# PR9025.net
KiCad netlist of a schematic drawn in EAGLE
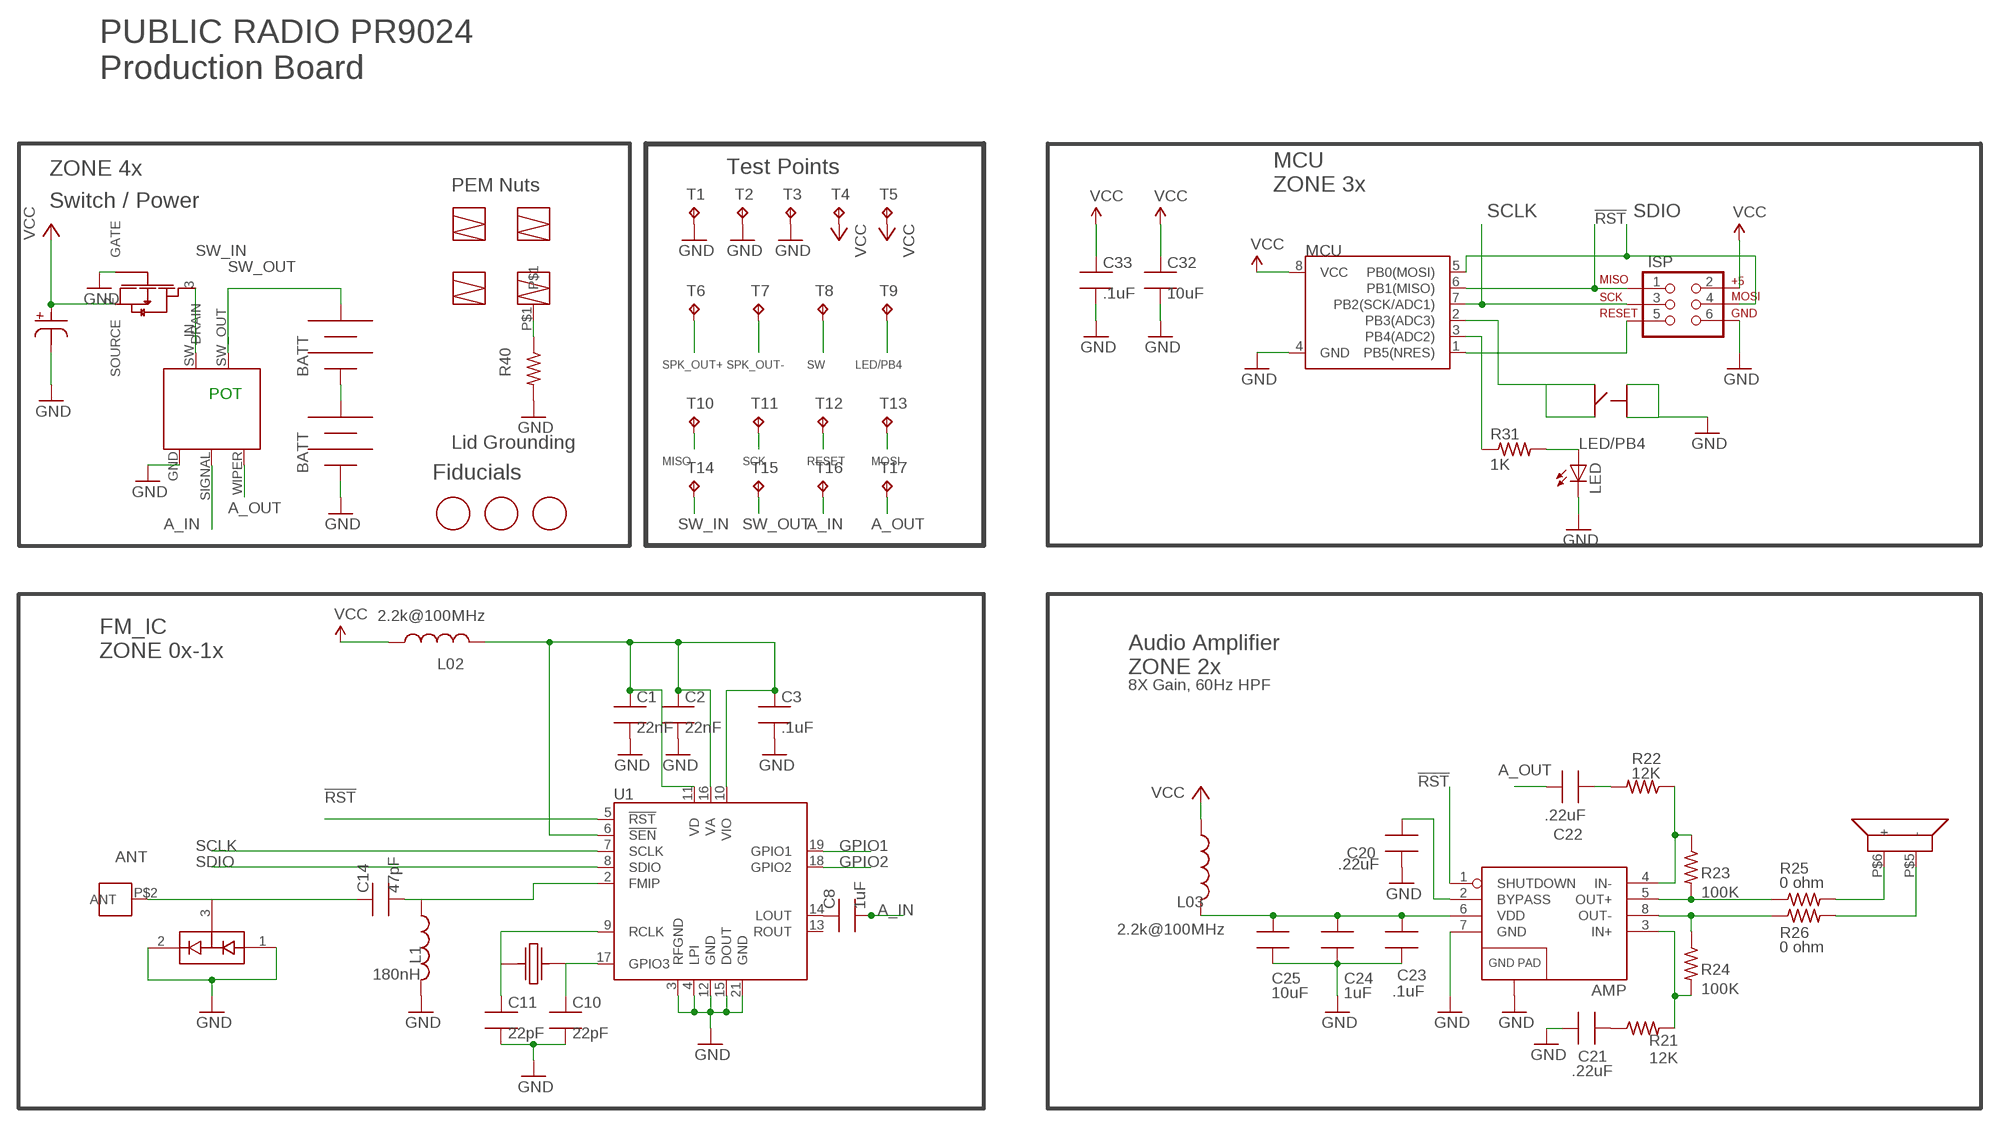
[diagram p0: schematic, sheet 1]

(export (version "E")
  (design (tool "Eeschema 10.0.6"))
  (components
    (comp (ref "AMP")
      (value "TPA6203A1")
      (footprint "eagle-import:8-MSOP")
      (libsource (lib "eagle-import") (part "TPA6203A1"))
    )
    (comp (ref "ANT_MOUNT")
      (value "DNP")
      (footprint "eagle-import:PEM_M3")
      (libsource (lib "eagle-import") (part "M3_PEMNUT"))
    )
    (comp (ref "C1")
      (value "22nF")
      (footprint "eagle-import:0603_CPL")
      (fields
        (field (name "MFG_PN") "CL10B223KB8NNNC")
        (field (name "TOL") "10%")
        (field (name "VOLTAGE") "16V")
      )
      (libsource (lib "eagle-import") (part "C_SMT_0603_CPL"))
    )
    (comp (ref "C2")
      (value "22nF")
      (footprint "eagle-import:0603_CPL")
      (fields
        (field (name "MFG_PN") "CL10B223KB8NNNC")
        (field (name "TOL") "10%")
        (field (name "VOLTAGE") "16V")
      )
      (libsource (lib "eagle-import") (part "C_SMT_0603_CPL"))
    )
    (comp (ref "C3")
      (value ".1uF")
      (footprint "eagle-import:0603_CPL")
      (fields
        (field (name "MFG_PN") "CL10B104KB8SFNC")
        (field (name "TOL") "10%")
        (field (name "VOLTAGE") "16V")
      )
      (libsource (lib "eagle-import") (part "C_SMT_0603_CPL"))
    )
    (comp (ref "C8")
      (value "1uF")
      (footprint "eagle-import:0603_CPL")
      (fields
        (field (name "MFG_PN") "CL10B105KP8NNNC")
        (field (name "TOL") "10%")
        (field (name "VOLTAGE") "10V")
      )
      (libsource (lib "eagle-import") (part "C_SMT_0603_CPL"))
    )
    (comp (ref "C10")
      (value "22pF")
      (footprint "eagle-import:0603_CPL")
      (fields
        (field (name "MFG_PN") "C1608C0G1H220J080AA")
        (field (name "TOL") "5%")
        (field (name "VOLTAGE") "50V")
      )
      (libsource (lib "eagle-import") (part "C_SMT_0603_CPL"))
    )
    (comp (ref "C11")
      (value "22pF")
      (footprint "eagle-import:0603_CPL")
      (fields
        (field (name "MFG_PN") "C1608C0G1H220J080AA")
        (field (name "TOL") "5%")
        (field (name "VOLTAGE") "50V")
      )
      (libsource (lib "eagle-import") (part "C_SMT_0603_CPL"))
    )
    (comp (ref "C14")
      (value "47pF")
      (footprint "eagle-import:0603_CPL")
      (fields
        (field (name "MFG_PN") "CL10C470JB8NCNC")
        (field (name "TOL") "5%")
        (field (name "VOLTAGE") "50V")
      )
      (libsource (lib "eagle-import") (part "C_SMT_0603_CPL"))
    )
    (comp (ref "C20")
      (value ".22uF")
      (footprint "eagle-import:0603_CPL")
      (fields
        (field (name "MFG_PN") "C1608X7R1C224K080AC")
        (field (name "TOL") "10%")
        (field (name "VOLTAGE") "16V")
      )
      (libsource (lib "eagle-import") (part "C_SMT_0603_CPL"))
    )
    (comp (ref "C21")
      (value ".22uF")
      (footprint "eagle-import:0603_CPL")
      (fields
        (field (name "MFG_PN") "C1608X7R1C224K080AC")
        (field (name "TOL") "10%")
        (field (name "VOLTAGE") "16V")
      )
      (libsource (lib "eagle-import") (part "C_SMT_0603_CPL"))
    )
    (comp (ref "C22")
      (value ".22uF")
      (footprint "eagle-import:0603_CPL")
      (fields
        (field (name "MFG_PN") "C1608X7R1C224K080AC")
        (field (name "TOL") "10%")
        (field (name "VOLTAGE") "16V")
      )
      (libsource (lib "eagle-import") (part "C_SMT_0603_CPL"))
    )
    (comp (ref "C23")
      (value ".1uF")
      (footprint "eagle-import:0603_CPL")
      (fields
        (field (name "MFG_PN") "CL10B104KB8SFNC")
        (field (name "TOL") "10%")
        (field (name "VOLTAGE") "16V")
      )
      (libsource (lib "eagle-import") (part "C_SMT_0603_CPL"))
    )
    (comp (ref "C24")
      (value "1uF")
      (footprint "eagle-import:0603_CPL")
      (fields
        (field (name "MFG_PN") "CL10B105KP8NNNC")
        (field (name "TOL") "10%")
        (field (name "VOLTAGE") "10V")
      )
      (libsource (lib "eagle-import") (part "C_SMT_0603_CPL"))
    )
    (comp (ref "C25")
      (value "10uF")
      (footprint "eagle-import:0603_CPL")
      (fields
        (field (name "MFG_PN") "CL10A106MQ8NNNC")
        (field (name "TOL") "20%")
        (field (name "VOLTAGE") "6.3V")
      )
      (libsource (lib "eagle-import") (part "C_SMT_0603_CPL"))
    )
    (comp (ref "C32")
      (value "10uF")
      (footprint "eagle-import:0603_CPL")
      (fields
        (field (name "MFG_PN") "CL10A106MQ8NNNC")
        (field (name "TOL") "20%")
        (field (name "VOLTAGE") "6.3V")
      )
      (libsource (lib "eagle-import") (part "C_SMT_0603_CPL"))
    )
    (comp (ref "C33")
      (value ".1uF")
      (footprint "eagle-import:0603_CPL")
      (fields
        (field (name "MFG_PN") "CL10B104KB8SFNC")
        (field (name "TOL") "10%")
        (field (name "VOLTAGE") "16V")
      )
      (libsource (lib "eagle-import") (part "C_SMT_0603_CPL"))
    )
    (comp (ref "C40")
      (value "220uF")
      (footprint "eagle-import:NICHICON_UD_63")
      (fields (field (name "TOL") "20%") (field (name "VOLTAGE") "16V"))
      (libsource (lib "eagle-import") (part "NICHICON_SERIESUD"))
    )
    (comp (ref "D1")
      (value "BAV99")
      (footprint "eagle-import:SOT23_CPL")
      (fields (field (name "MFG_PN") "BAV99,215"))
      (libsource (lib "eagle-import") (part "BAV99"))
    )
    (comp (ref "FET1")
      (value "AO3435")
      (footprint "eagle-import:SOT23_CPL")
      (fields (field (name "MFG_PN") "AO3435"))
      (libsource (lib "eagle-import") (part "AO3435"))
    )
    (comp (ref "ISP")
      (value "AVR_SPI_PRG_6NS")
      (footprint "eagle-import:2X3-NS")
      (libsource (lib "eagle-import") (part "AVR_SPI_PRG_6NS"))
    )
    (comp (ref "JP5")
      (value "BK-92_MPD_AA_BATT_CLIP")
      (footprint "eagle-import:BK92_AA_BATT")
      (fields (field (name "MFG_PN") "2 of BK92 - supplied by CL Labs"))
      (libsource (lib "eagle-import") (part "BK-92_MPD_AA_BATT_CLIP"))
    )
    (comp (ref "JP6")
      (value "BK-92_MPD_AA_BATT_CLIP")
      (footprint "eagle-import:BK92_AA_BATT")
      (fields (field (name "MFG_PN") "2 of BK92 - supplied by CL Labs"))
      (libsource (lib "eagle-import") (part "BK-92_MPD_AA_BATT_CLIP"))
    )
    (comp (ref "L1")
      (value "180nH")
      (footprint "eagle-import:0805_ADAFRUIT")
      (fields
        (field (name "CURRENT") "400mA")
        (field (name "DCR") "640m")
        (field (name "MFG_PN") "AISC-0805-R18J-T")
        (field (name "TOL") "5%")
      )
      (libsource (lib "eagle-import") (part "L_SMT_0805_ADAFRUIT"))
    )
    (comp (ref "L02")
      (value "2.2k@100MHz")
      (footprint "eagle-import:0603_CPL")
      (fields
        (field (name "CURRENT") "150mA")
        (field (name "DCR") "2.3")
        (field (name "MFG_PN") "HZ0603A222R-10")
      )
      (libsource (lib "eagle-import") (part "L_SMT_0603_CPL"))
    )
    (comp (ref "L03")
      (value "2.2k@100MHz")
      (footprint "eagle-import:0603_CPL")
      (fields
        (field (name "CURRENT") "150mA")
        (field (name "DCR") "2.3")
        (field (name "MFG_PN") "HZ0603A222R-10")
      )
      (libsource (lib "eagle-import") (part "L_SMT_0603_CPL"))
    )
    (comp (ref "LED")
      (value "HSMC-C265_REVERSE_MOUNT_LED")
      (footprint "eagle-import:HSMC-C265_REVERSE_MOUN_LED")
      (libsource (lib "eagle-import") (part "HSMC-C265_REVERSE_MOUNT_LED"))
    )
    (comp (ref "MARK1")
      (value "FIDUCIAL")
      (footprint "eagle-import:FIDUCIAL_1MM")
      (libsource (lib "eagle-import") (part "FIDUCIAL"))
    )
    (comp (ref "MARK2")
      (value "FIDUCIAL")
      (footprint "eagle-import:FIDUCIAL_1MM")
      (libsource (lib "eagle-import") (part "FIDUCIAL"))
    )
    (comp (ref "MARK3")
      (value "FIDUCIAL")
      (footprint "eagle-import:FIDUCIAL_1MM")
      (libsource (lib "eagle-import") (part "FIDUCIAL"))
    )
    (comp (ref "MCU")
      (value "ATTINY45TINY45-20-SMT")
      (footprint "eagle-import:8-SOIC")
      (libsource (lib "eagle-import") (part "ATTINY45TINY45-20-SMT"))
    )
    (comp (ref "R1")
      (value "VOLUME_POT")
      (footprint "eagle-import:H17112NS_A10K_L20F-002")
      (libsource (lib "eagle-import") (part "VOLUME_POT"))
    )
    (comp (ref "R21")
      (value "12K")
      (footprint "eagle-import:0603_CPL")
      (fields
        (field (name "MFG_PN") "RC0603FR-0712KL")
        (field (name "POWER") "1/10W")
        (field (name "TOL") "1%")
      )
      (libsource (lib "eagle-import") (part "R_SMT_R0603_CPL"))
    )
    (comp (ref "R22")
      (value "12K")
      (footprint "eagle-import:0603_CPL")
      (fields
        (field (name "MFG_PN") "RC0603FR-0712KL")
        (field (name "POWER") "1/10W")
        (field (name "TOL") "1%")
      )
      (libsource (lib "eagle-import") (part "R_SMT_R0603_CPL"))
    )
    (comp (ref "R23")
      (value "100K")
      (footprint "eagle-import:0603_CPL")
      (fields
        (field (name "MFG_PN") "ERJ-3EKF1003V")
        (field (name "POWER") "1/10W")
        (field (name "TOL") "1%")
      )
      (libsource (lib "eagle-import") (part "R_SMT_R0603_CPL"))
    )
    (comp (ref "R24")
      (value "100K")
      (footprint "eagle-import:0603_CPL")
      (fields
        (field (name "MFG_PN") "ERJ-3EKF1003V")
        (field (name "POWER") "1/10W")
        (field (name "TOL") "1%")
      )
      (libsource (lib "eagle-import") (part "R_SMT_R0603_CPL"))
    )
    (comp (ref "R25")
      (value "0 ohm")
      (footprint "eagle-import:0805_ADAFRUIT")
      (fields (field (name "MFG_PN") "ERJ-6GEY0R00V "))
      (libsource (lib "eagle-import") (part "R_SMT_0805_ADAFRUIT"))
    )
    (comp (ref "R26")
      (value "0 ohm")
      (footprint "eagle-import:0805_ADAFRUIT")
      (fields (field (name "MFG_PN") "ERJ-6GEY0R00V "))
      (libsource (lib "eagle-import") (part "R_SMT_0805_ADAFRUIT"))
    )
    (comp (ref "R31")
      (value "1K")
      (footprint "eagle-import:0603_CPL")
      (fields (field (name "MFG_PN") "311-1.00KHRCT-ND"))
      (libsource (lib "eagle-import") (part "R_SMT_R0603_CPL"))
    )
    (comp (ref "R40")
      (value "DNP")
      (footprint "eagle-import:0603_CPL")
      (fields (field (name "MFG_PN") "ERJ-3GEY0R00V"))
      (libsource (lib "eagle-import") (part "R_SMT_R0603_CPL"))
    )
    (comp (ref "SPKR_PLACE")
      (value "DNP")
      (footprint "eagle-import:PR2024_SPKR_PLACE(SMD)")
      (libsource (lib "eagle-import") (part "PR2024_SPKR_SMD"))
    )
    (comp (ref "SW1")
      (value "C&K_PTS645")
      (footprint "eagle-import:C&K_PTS645_SMT")
      (libsource (lib "eagle-import") (part "C&K_PTS645"))
    )
    (comp (ref "T1")
      (value "TPTP20R")
      (footprint "eagle-import:TP20R")
      (libsource (lib "eagle-import") (part "TPTP20R"))
    )
    (comp (ref "T2")
      (value "TPTP20R")
      (footprint "eagle-import:TP20R")
      (libsource (lib "eagle-import") (part "TPTP20R"))
    )
    (comp (ref "T3")
      (value "TPTP20R")
      (footprint "eagle-import:TP20R")
      (libsource (lib "eagle-import") (part "TPTP20R"))
    )
    (comp (ref "T4")
      (value "TPTP20R")
      (footprint "eagle-import:TP20R")
      (libsource (lib "eagle-import") (part "TPTP20R"))
    )
    (comp (ref "T5")
      (value "TPTP20R")
      (footprint "eagle-import:TP20R")
      (libsource (lib "eagle-import") (part "TPTP20R"))
    )
    (comp (ref "T6")
      (value "TPTP20R")
      (footprint "eagle-import:TP20R")
      (libsource (lib "eagle-import") (part "TPTP20R"))
    )
    (comp (ref "T7")
      (value "TPTP20R")
      (footprint "eagle-import:TP20R")
      (libsource (lib "eagle-import") (part "TPTP20R"))
    )
    (comp (ref "T8")
      (value "TPTP20R")
      (footprint "eagle-import:TP20R")
      (libsource (lib "eagle-import") (part "TPTP20R"))
    )
    (comp (ref "T9")
      (value "TPTP20R")
      (footprint "eagle-import:TP20R")
      (libsource (lib "eagle-import") (part "TPTP20R"))
    )
    (comp (ref "T10")
      (value "TPTP20R")
      (footprint "eagle-import:TP20R")
      (libsource (lib "eagle-import") (part "TPTP20R"))
    )
    (comp (ref "T11")
      (value "TPTP20R")
      (footprint "eagle-import:TP20R")
      (libsource (lib "eagle-import") (part "TPTP20R"))
    )
    (comp (ref "T12")
      (value "TPTP20R")
      (footprint "eagle-import:TP20R")
      (libsource (lib "eagle-import") (part "TPTP20R"))
    )
    (comp (ref "T13")
      (value "TPTP20R")
      (footprint "eagle-import:TP20R")
      (libsource (lib "eagle-import") (part "TPTP20R"))
    )
    (comp (ref "T14")
      (value "TPTP20R")
      (footprint "eagle-import:TP20R")
      (libsource (lib "eagle-import") (part "TPTP20R"))
    )
    (comp (ref "T15")
      (value "TPTP20R")
      (footprint "eagle-import:TP20R")
      (libsource (lib "eagle-import") (part "TPTP20R"))
    )
    (comp (ref "T16")
      (value "TPTP20R")
      (footprint "eagle-import:TP20R")
      (libsource (lib "eagle-import") (part "TPTP20R"))
    )
    (comp (ref "T17")
      (value "TPTP20R")
      (footprint "eagle-import:TP20R")
      (libsource (lib "eagle-import") (part "TPTP20R"))
    )
    (comp (ref "U$2")
      (value "PEM_SMT")
      (footprint "eagle-import:PEM_SMT")
      (libsource (lib "eagle-import") (part "PEM_SMT"))
    )
    (comp (ref "U$3")
      (value "PEM_SMT")
      (footprint "eagle-import:PEM_SMT")
      (libsource (lib "eagle-import") (part "PEM_SMT"))
    )
    (comp (ref "U$4")
      (value "PEM_SMT")
      (footprint "eagle-import:PEM_SMT")
      (libsource (lib "eagle-import") (part "PEM_SMT"))
    )
    (comp (ref "U$5")
      (value "PEM_M3_SMT_W/PIN")
      (footprint "eagle-import:PEM_SMT")
      (libsource (lib "eagle-import") (part "PEM_M3_SMT_W/PIN"))
    )
    (comp (ref "U1")
      (value "SI4702-C19-GMR")
      (footprint "eagle-import:SI470X_20_QFN")
      (fields (field (name "MFG_PN") "Si4702 C19 GM - supplied by CL Labs"))
      (libsource (lib "eagle-import") (part "SI4702-C19-GMR"))
    )
    (comp (ref "X1")
      (value "ABS25XTAL")
      (footprint "eagle-import:4-SOJ")
      (libsource (lib "eagle-import") (part "ABS25XTAL"))
    )
  )
  (nets
    (net (code "1") (name "/ANT") (class "Default")
      (node (ref "ANT_MOUNT") (pin "P$2") (pinfunction "ANT_P$2") (pintype "bidirectional"))
      (node (ref "C14") (pin "1") (pinfunction "1_1") (pintype "passive"))
      (node (ref "D1") (pin "3") (pinfunction "COM_3") (pintype "bidirectional"))
    )
    (net (code "2") (name "/A_IN") (class "Default")
      (node (ref "C8") (pin "2") (pinfunction "2_2") (pintype "passive"))
      (node (ref "R1") (pin "SIGNAL") (pinfunction "SIGNAL_SIGNAL") (pintype "bidirectional"))
      (node (ref "T16") (pin "TP") (pinfunction "TP_TP") (pintype "input"))
    )
    (net (code "3") (name "/A_OUT") (class "Default")
      (node (ref "C22") (pin "2") (pinfunction "2_2") (pintype "passive"))
      (node (ref "R1") (pin "WIPER") (pinfunction "WIPER_WIPER") (pintype "bidirectional"))
      (node (ref "T17") (pin "TP") (pinfunction "TP_TP") (pintype "input"))
    )
    (net (code "4") (name "/GPIO1") (class "Default")
      (node (ref "U1") (pin "19") (pinfunction "GPIO1_19") (pintype "bidirectional"))
    )
    (net (code "5") (name "/GPIO2") (class "Default")
      (node (ref "U1") (pin "18") (pinfunction "GPIO2_18") (pintype "bidirectional"))
    )
    (net (code "6") (name "/LED{slash}PB4") (class "Default")
      (node (ref "MCU") (pin "3") (pinfunction "PB4(ADC2)_3") (pintype "bidirectional"))
      (node (ref "R31") (pin "1") (pinfunction "1_1") (pintype "passive"))
      (node (ref "T9") (pin "TP") (pinfunction "TP_TP") (pintype "input"))
    )
    (net (code "7") (name "/RESET") (class "Default")
      (node (ref "ISP") (pin "5") (pinfunction "5_5") (pintype "passive"))
      (node (ref "MCU") (pin "1") (pinfunction "PB5(NRES)_1") (pintype "bidirectional"))
      (node (ref "T12") (pin "TP") (pinfunction "TP_TP") (pintype "input"))
    )
    (net (code "8") (name "/SCLK") (class "Default")
      (node (ref "ISP") (pin "3") (pinfunction "3_3") (pintype "passive"))
      (node (ref "MCU") (pin "7") (pinfunction "PB2(SCK/ADC1)_7") (pintype "bidirectional"))
      (node (ref "T11") (pin "TP") (pinfunction "TP_TP") (pintype "input"))
      (node (ref "U1") (pin "7") (pinfunction "SCLK_7") (pintype "bidirectional"))
    )
    (net (code "9") (name "/SDIO") (class "Default")
      (node (ref "ISP") (pin "4") (pinfunction "4_4") (pintype "passive"))
      (node (ref "MCU") (pin "5") (pinfunction "PB0(MOSI)_5") (pintype "bidirectional"))
      (node (ref "T13") (pin "TP") (pinfunction "TP_TP") (pintype "input"))
      (node (ref "U1") (pin "8") (pinfunction "SDIO_8") (pintype "bidirectional"))
    )
    (net (code "10") (name "/SPK_OUT+") (class "Default")
      (node (ref "R25") (pin "2") (pinfunction "2_2") (pintype "passive"))
      (node (ref "SPKR_PLACE") (pin "P$6") (pinfunction "+_P$6") (pintype "bidirectional"))
      (node (ref "T6") (pin "TP") (pinfunction "TP_TP") (pintype "input"))
    )
    (net (code "11") (name "/SPK_OUT-") (class "Default")
      (node (ref "R26") (pin "2") (pinfunction "2_2") (pintype "passive"))
      (node (ref "SPKR_PLACE") (pin "P$5") (pinfunction "-_P$5") (pintype "bidirectional"))
      (node (ref "T7") (pin "TP") (pinfunction "TP_TP") (pintype "input"))
    )
    (net (code "12") (name "/SW") (class "Default")
      (node (ref "MCU") (pin "2") (pinfunction "PB3(ADC3)_2") (pintype "bidirectional"))
      (node (ref "SW1") (pin "P$3") (pinfunction "P$3_P$3") (pintype "bidirectional"))
      (node (ref "SW1") (pin "P$4") (pinfunction "P$4_P$4") (pintype "bidirectional"))
      (node (ref "T8") (pin "TP") (pinfunction "TP_TP") (pintype "input"))
    )
    (net (code "13") (name "/SW_IN") (class "Default")
      (node (ref "FET1") (pin "3") (pinfunction "DRAIN_3") (pintype "bidirectional"))
      (node (ref "R1") (pin "SW_IN") (pinfunction "SW_IN_SW_IN") (pintype "bidirectional"))
      (node (ref "T14") (pin "TP") (pinfunction "TP_TP") (pintype "input"))
    )
    (net (code "14") (name "/SW_OUT") (class "Default")
      (node (ref "JP5") (pin "POS") (pinfunction "POS_POS") (pintype "bidirectional"))
      (node (ref "JP5") (pin "POS@2") (pinfunction "POS_POS@2") (pintype "bidirectional"))
      (node (ref "R1") (pin "SW_OUT") (pinfunction "SW_OUT_SW_OUT") (pintype "bidirectional"))
      (node (ref "T15") (pin "TP") (pinfunction "TP_TP") (pintype "input"))
    )
    (net (code "15") (name "/~{RST}") (class "Default")
      (node (ref "AMP") (pin "1") (pinfunction "SHUTDOWN_1") (pintype "input"))
      (node (ref "ISP") (pin "1") (pinfunction "1_1") (pintype "passive"))
      (node (ref "MCU") (pin "6") (pinfunction "PB1(MISO)_6") (pintype "bidirectional"))
      (node (ref "T10") (pin "TP") (pinfunction "TP_TP") (pintype "input"))
      (node (ref "U1") (pin "5") (pinfunction "~{RST}_5") (pintype "bidirectional"))
    )
    (net (code "16") (name "GND") (class "Default")
      (node (ref "AMP") (pin "7") (pinfunction "GND_7") (pintype "power_in"))
      (node (ref "AMP") (pin "9") (pinfunction "GND_9") (pintype "power_in"))
      (node (ref "C1") (pin "2") (pinfunction "2_2") (pintype "passive"))
      (node (ref "C10") (pin "2") (pinfunction "2_2") (pintype "passive"))
      (node (ref "C11") (pin "2") (pinfunction "2_2") (pintype "passive"))
      (node (ref "C2") (pin "2") (pinfunction "2_2") (pintype "passive"))
      (node (ref "C20") (pin "1") (pinfunction "1_1") (pintype "passive"))
      (node (ref "C21") (pin "1") (pinfunction "1_1") (pintype "passive"))
      (node (ref "C23") (pin "2") (pinfunction "2_2") (pintype "passive"))
      (node (ref "C24") (pin "2") (pinfunction "2_2") (pintype "passive"))
      (node (ref "C25") (pin "2") (pinfunction "2_2") (pintype "passive"))
      (node (ref "C3") (pin "2") (pinfunction "2_2") (pintype "passive"))
      (node (ref "C32") (pin "2") (pinfunction "2_2") (pintype "passive"))
      (node (ref "C33") (pin "2") (pinfunction "2_2") (pintype "passive"))
      (node (ref "C40") (pin "P$2") (pinfunction "P$2_P$2") (pintype "bidirectional"))
      (node (ref "D1") (pin "1") (pinfunction "A1_1") (pintype "bidirectional"))
      (node (ref "D1") (pin "2") (pinfunction "C2_2") (pintype "bidirectional"))
      (node (ref "FET1") (pin "1") (pinfunction "GATE_1") (pintype "bidirectional"))
      (node (ref "ISP") (pin "6") (pinfunction "6_6") (pintype "passive"))
      (node (ref "JP6") (pin "NEG") (pinfunction "NEG_NEG") (pintype "bidirectional"))
      (node (ref "JP6") (pin "NEG@2") (pinfunction "NEG_NEG@2") (pintype "bidirectional"))
      (node (ref "L1") (pin "2") (pinfunction "2_2") (pintype "passive"))
      (node (ref "LED") (pin "P$2") (pinfunction "C_P$2") (pintype "passive"))
      (node (ref "MCU") (pin "4") (pinfunction "GND_4") (pintype "bidirectional"))
      (node (ref "R1") (pin "GND") (pinfunction "GND_GND") (pintype "bidirectional"))
      (node (ref "R40") (pin "2") (pinfunction "2_2") (pintype "passive"))
      (node (ref "SW1") (pin "P$1") (pinfunction "P$1_P$1") (pintype "bidirectional"))
      (node (ref "SW1") (pin "P$2") (pinfunction "P$2_P$2") (pintype "bidirectional"))
      (node (ref "T1") (pin "TP") (pinfunction "TP_TP") (pintype "input"))
      (node (ref "T2") (pin "TP") (pinfunction "TP_TP") (pintype "input"))
      (node (ref "T3") (pin "TP") (pinfunction "TP_TP") (pintype "input"))
      (node (ref "U1") (pin "12") (pinfunction "GND_12") (pintype "bidirectional"))
      (node (ref "U1") (pin "15") (pinfunction "DOUT_15") (pintype "bidirectional"))
      (node (ref "U1") (pin "21") (pinfunction "GND_21") (pintype "bidirectional"))
      (node (ref "U1") (pin "3") (pinfunction "RFGND_3") (pintype "bidirectional"))
      (node (ref "U1") (pin "4") (pinfunction "LPI_4") (pintype "bidirectional"))
    )
    (net (code "17") (name "Net-(AMP-BYPASS)") (class "Default")
      (node (ref "AMP") (pin "2") (pinfunction "BYPASS_2") (pintype "bidirectional"))
      (node (ref "C20") (pin "2") (pinfunction "2_2") (pintype "passive"))
    )
    (net (code "18") (name "Net-(AMP-IN+)") (class "Default")
      (node (ref "AMP") (pin "3") (pinfunction "IN+_3") (pintype "bidirectional"))
      (node (ref "R21") (pin "2") (pinfunction "2_2") (pintype "passive"))
      (node (ref "R24") (pin "2") (pinfunction "2_2") (pintype "passive"))
    )
    (net (code "19") (name "Net-(AMP-IN-)") (class "Default")
      (node (ref "AMP") (pin "4") (pinfunction "IN-_4") (pintype "bidirectional"))
      (node (ref "R22") (pin "1") (pinfunction "1_1") (pintype "passive"))
      (node (ref "R23") (pin "1") (pinfunction "1_1") (pintype "passive"))
    )
    (net (code "20") (name "Net-(AMP-OUT+)") (class "Default")
      (node (ref "AMP") (pin "5") (pinfunction "OUT+_5") (pintype "bidirectional"))
      (node (ref "R23") (pin "2") (pinfunction "2_2") (pintype "passive"))
      (node (ref "R25") (pin "1") (pinfunction "1_1") (pintype "passive"))
    )
    (net (code "21") (name "Net-(AMP-OUT-)") (class "Default")
      (node (ref "AMP") (pin "8") (pinfunction "OUT-_8") (pintype "bidirectional"))
      (node (ref "R24") (pin "1") (pinfunction "1_1") (pintype "passive"))
      (node (ref "R26") (pin "1") (pinfunction "1_1") (pintype "passive"))
    )
    (net (code "22") (name "Net-(AMP-VDD)") (class "Default")
      (node (ref "AMP") (pin "6") (pinfunction "VDD_6") (pintype "power_in"))
      (node (ref "C23") (pin "1") (pinfunction "1_1") (pintype "passive"))
      (node (ref "C24") (pin "1") (pinfunction "1_1") (pintype "passive"))
      (node (ref "C25") (pin "1") (pinfunction "1_1") (pintype "passive"))
      (node (ref "L03") (pin "2") (pinfunction "2_2") (pintype "passive"))
    )
    (net (code "23") (name "Net-(C21-Pad2)") (class "Default")
      (node (ref "C21") (pin "2") (pinfunction "2_2") (pintype "passive"))
      (node (ref "R21") (pin "1") (pinfunction "1_1") (pintype "passive"))
    )
    (net (code "24") (name "Net-(C22-Pad1)") (class "Default")
      (node (ref "C22") (pin "1") (pinfunction "1_1") (pintype "passive"))
      (node (ref "R22") (pin "2") (pinfunction "2_2") (pintype "passive"))
    )
    (net (code "25") (name "Net-(JP5-NEG-PadNEG@2)") (class "Default")
      (node (ref "JP5") (pin "NEG") (pinfunction "NEG_NEG") (pintype "bidirectional"))
      (node (ref "JP5") (pin "NEG@2") (pinfunction "NEG_NEG@2") (pintype "bidirectional"))
      (node (ref "JP6") (pin "POS") (pinfunction "POS_POS") (pintype "bidirectional"))
      (node (ref "JP6") (pin "POS@2") (pinfunction "POS_POS@2") (pintype "bidirectional"))
    )
    (net (code "26") (name "Net-(LED-A)") (class "Default")
      (node (ref "LED") (pin "P$1") (pinfunction "A_P$1") (pintype "passive"))
      (node (ref "R31") (pin "2") (pinfunction "2_2") (pintype "passive"))
    )
    (net (code "27") (name "Net-(R40-Pad1)") (class "Default")
      (node (ref "R40") (pin "1") (pinfunction "1_1") (pintype "passive"))
      (node (ref "U$5") (pin "P$1") (pinfunction "P$1_P$1") (pintype "bidirectional"))
    )
    (net (code "28") (name "Net-(U1-FMIP)") (class "Default")
      (node (ref "C14") (pin "2") (pinfunction "2_2") (pintype "passive"))
      (node (ref "L1") (pin "1") (pinfunction "1_1") (pintype "passive"))
      (node (ref "U1") (pin "2") (pinfunction "FMIP_2") (pintype "bidirectional"))
    )
    (net (code "29") (name "Net-(U1-GPIO3)") (class "Default")
      (node (ref "C10") (pin "1") (pinfunction "1_1") (pintype "passive"))
      (node (ref "U1") (pin "17") (pinfunction "GPIO3_17") (pintype "bidirectional"))
      (node (ref "X1") (pin "P$4") (pinfunction "P$4_P$4") (pintype "bidirectional"))
    )
    (net (code "30") (name "Net-(U1-LOUT)") (class "Default")
      (node (ref "C8") (pin "1") (pinfunction "1_1") (pintype "passive"))
      (node (ref "U1") (pin "14") (pinfunction "LOUT_14") (pintype "bidirectional"))
    )
    (net (code "31") (name "Net-(U1-RCLK)") (class "Default")
      (node (ref "C11") (pin "1") (pinfunction "1_1") (pintype "passive"))
      (node (ref "U1") (pin "9") (pinfunction "RCLK_9") (pintype "bidirectional"))
      (node (ref "X1") (pin "P$1") (pinfunction "P$1_P$1") (pintype "bidirectional"))
    )
    (net (code "32") (name "Net-(U1-VA)") (class "Default")
      (node (ref "C1") (pin "1") (pinfunction "1_1") (pintype "passive"))
      (node (ref "C2") (pin "1") (pinfunction "1_1") (pintype "passive"))
      (node (ref "C3") (pin "1") (pinfunction "1_1") (pintype "passive"))
      (node (ref "L02") (pin "2") (pinfunction "2_2") (pintype "passive"))
      (node (ref "U1") (pin "10") (pinfunction "VIO_10") (pintype "bidirectional"))
      (node (ref "U1") (pin "11") (pinfunction "VD_11") (pintype "bidirectional"))
      (node (ref "U1") (pin "16") (pinfunction "VA_16") (pintype "bidirectional"))
      (node (ref "U1") (pin "6") (pinfunction "~{SEN}_6") (pintype "bidirectional"))
    )
    (net (code "33") (name "VCC") (class "Default")
      (node (ref "C32") (pin "1") (pinfunction "1_1") (pintype "passive"))
      (node (ref "C33") (pin "1") (pinfunction "1_1") (pintype "passive"))
      (node (ref "C40") (pin "P$1") (pinfunction "P$1_P$1") (pintype "bidirectional"))
      (node (ref "FET1") (pin "2") (pinfunction "SOURCE_2") (pintype "bidirectional"))
      (node (ref "ISP") (pin "2") (pinfunction "2_2") (pintype "passive"))
      (node (ref "L02") (pin "1") (pinfunction "1_1") (pintype "passive"))
      (node (ref "L03") (pin "1") (pinfunction "1_1") (pintype "passive"))
      (node (ref "MCU") (pin "8") (pinfunction "VCC_8") (pintype "bidirectional"))
      (node (ref "T4") (pin "TP") (pinfunction "TP_TP") (pintype "input"))
      (node (ref "T5") (pin "TP") (pinfunction "TP_TP") (pintype "input"))
    )
    (net (code "34") (name "unconnected-(U1-ROUT-Pad13)") (class "Default")
      (node (ref "U1") (pin "13") (pinfunction "ROUT_13") (pintype "bidirectional"))
    )
  )
)
